# A_D_000000_001.net
KiCad netlist of a schematic drawn in Altium Designer
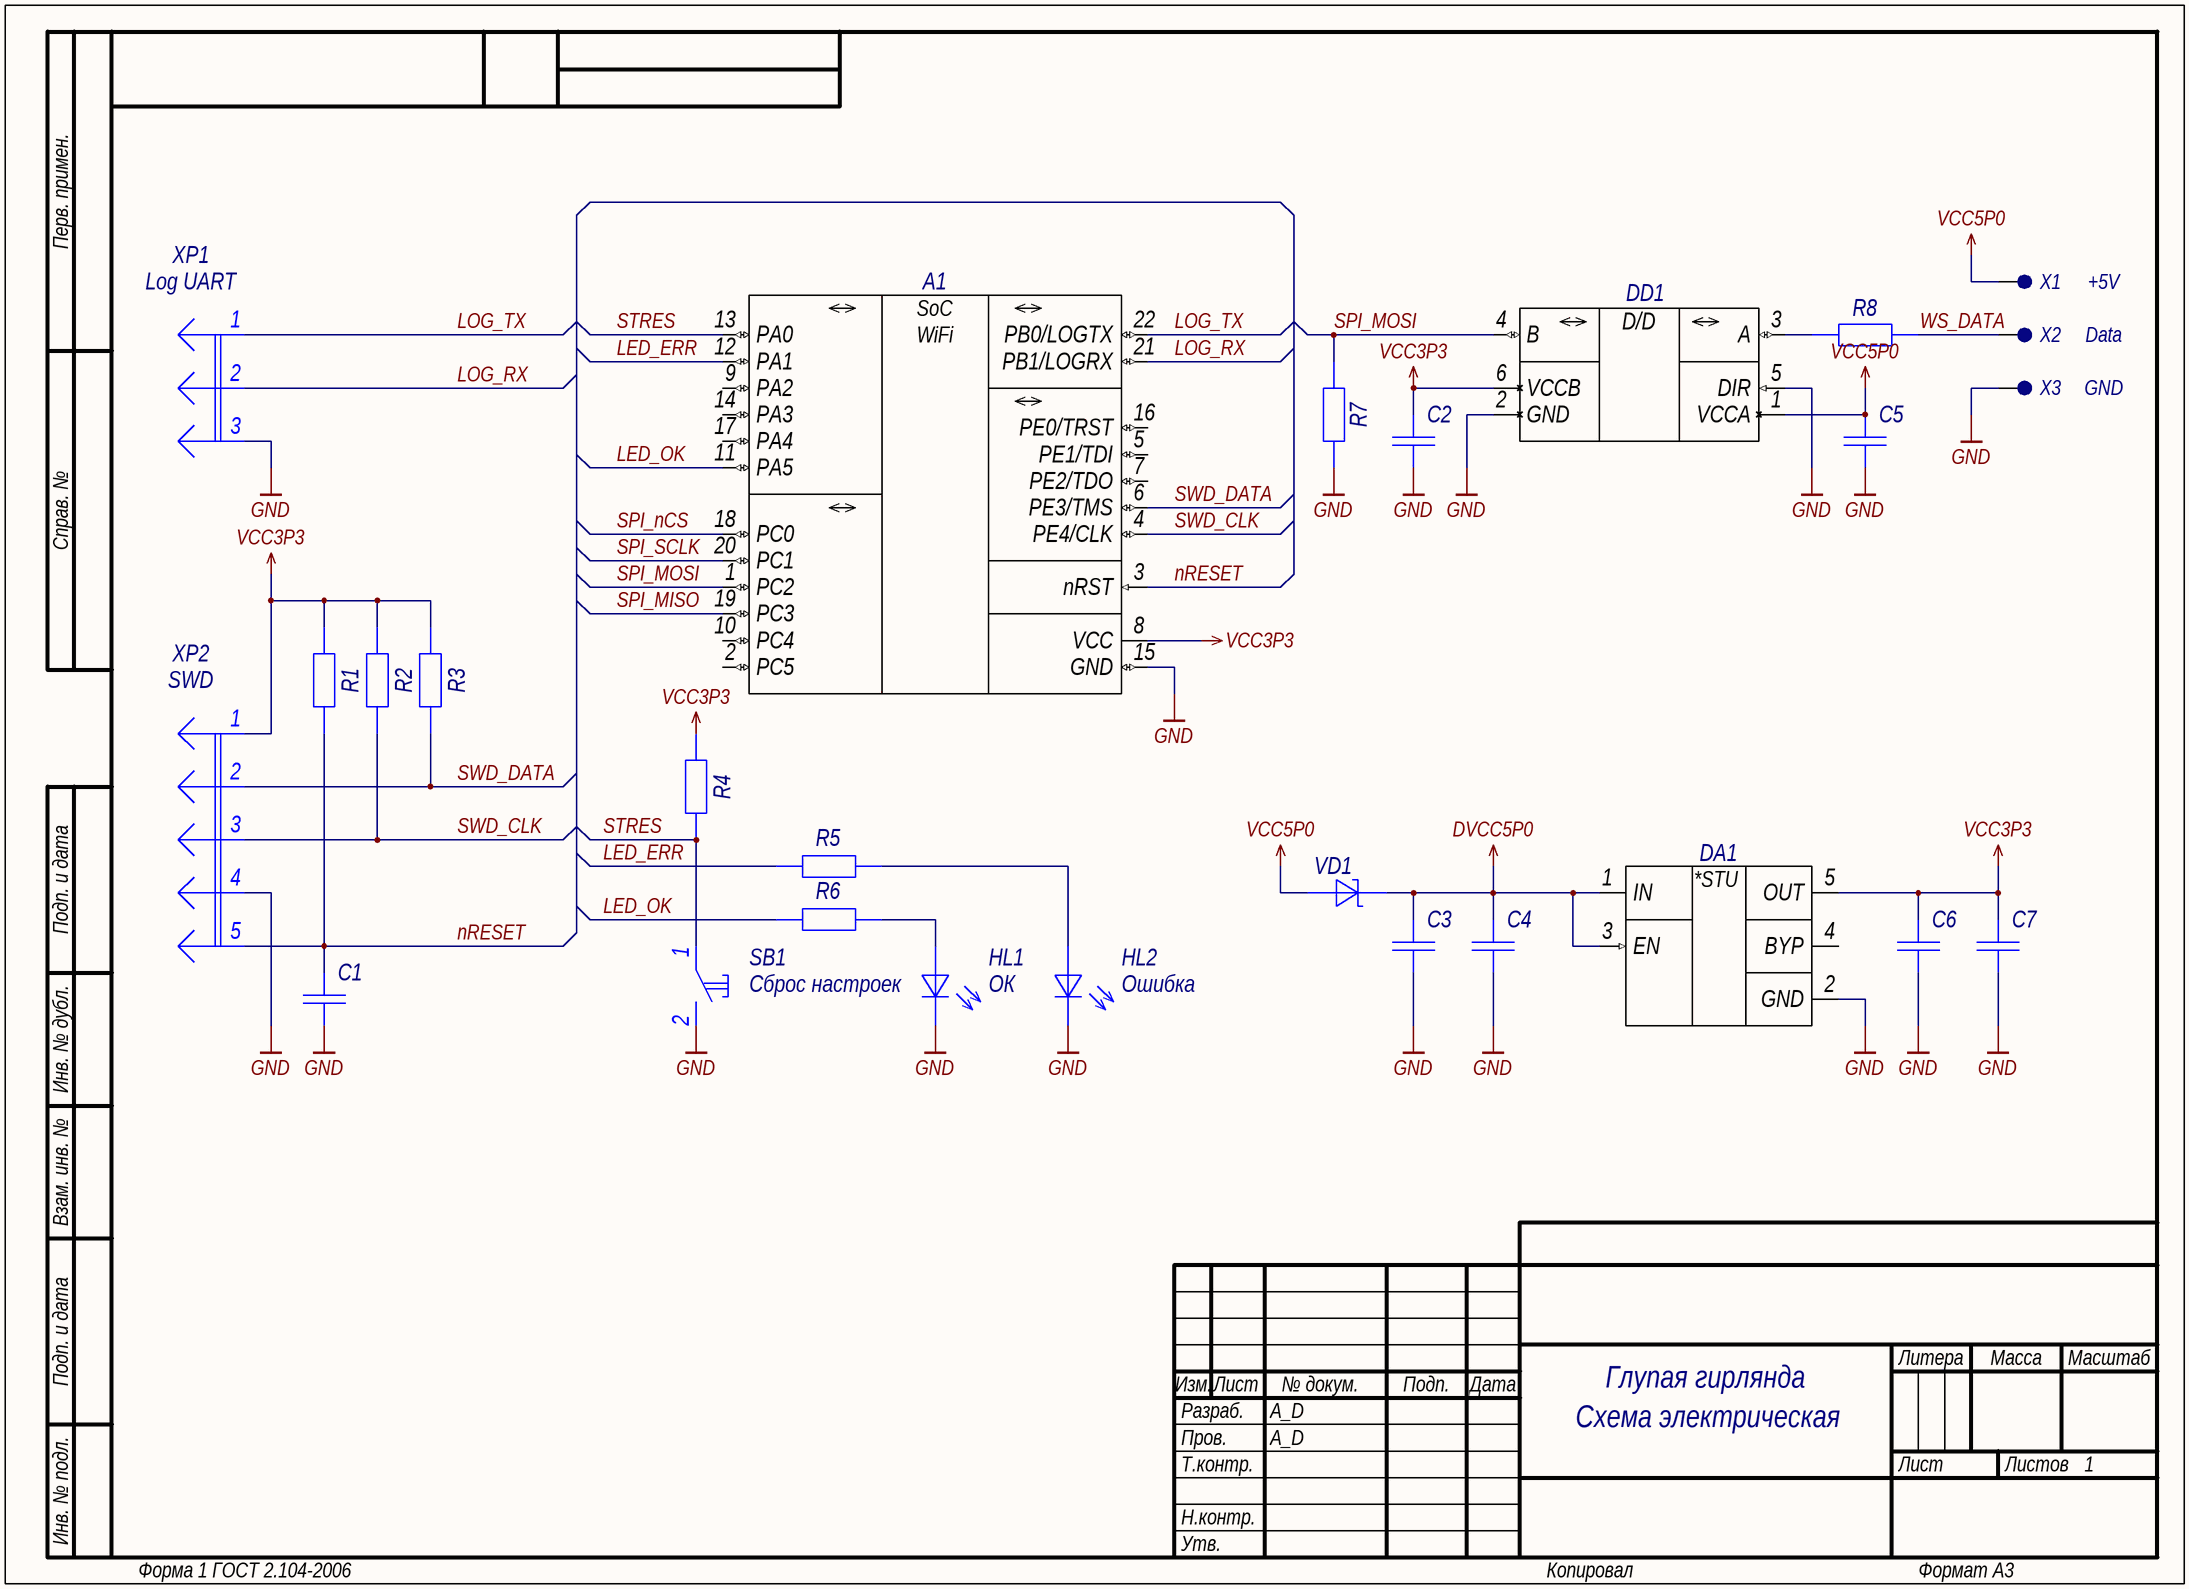
[diagram p0: A_D.000000.001.SchDoc]

(export (version "E")
  (design (tool "Eeschema 10.0.6"))
  (components
    (comp (ref "A1")
      (value "RTL-00_01")
      (footprint "RTL-00")
      (fields
        (field (name "PART NUMBER") "RTL-00")
        (field (name "MANUFACTURER") "B&T")
        (field (name "PUBLISHER") "Andrew Danich")
      )
      (libsource (lib "Lib_IMP_GOST") (part "RTL-00_01"))
    )
    (comp (ref "C1")
      (value "Capacitor")
      (footprint "C0603")
      (fields
        (field (name "PART NUMBER") "GRM188R71C104KA01D")
        (field (name "VOLTAGE") "16V")
        (field (name "TOLERANCE") "±10%")
        (field (name "PUBLISHER") "Andrew Danich")
      )
      (libsource (lib "Lib_IMP_GOST") (part "Capacitor"))
    )
    (comp (ref "C2")
      (value "Capacitor")
      (footprint "C0603")
      (fields
        (field (name "PART NUMBER") "GRM188R71C104KA01D")
        (field (name "VOLTAGE") "16V")
        (field (name "TOLERANCE") "±10%")
        (field (name "PUBLISHER") "Andrew Danich")
      )
      (libsource (lib "Lib_IMP_GOST") (part "Capacitor"))
    )
    (comp (ref "C3")
      (value "Capacitor")
      (footprint "C0805")
      (fields
        (field (name "PART NUMBER") "GRM21BR60J226ME39L")
        (field (name "VOLTAGE") "6.3V")
        (field (name "TOLERANCE") "±20%")
        (field (name "PUBLISHER") "Andrew Danich")
      )
      (libsource (lib "Lib_IMP_GOST") (part "Capacitor"))
    )
    (comp (ref "C4")
      (value "Capacitor")
      (footprint "C0603")
      (fields
        (field (name "PART NUMBER") "GRM188R71C104KA01D")
        (field (name "VOLTAGE") "16V")
        (field (name "TOLERANCE") "±10%")
        (field (name "PUBLISHER") "Andrew Danich")
      )
      (libsource (lib "Lib_IMP_GOST") (part "Capacitor"))
    )
    (comp (ref "C5")
      (value "Capacitor")
      (footprint "C0603")
      (fields
        (field (name "PART NUMBER") "GRM188R71C104KA01D")
        (field (name "VOLTAGE") "16V")
        (field (name "TOLERANCE") "±10%")
        (field (name "PUBLISHER") "Andrew Danich")
      )
      (libsource (lib "Lib_IMP_GOST") (part "Capacitor"))
    )
    (comp (ref "C6")
      (value "Capacitor")
      (footprint "C0603")
      (fields
        (field (name "PART NUMBER") "GRM188R71C104KA01D")
        (field (name "VOLTAGE") "16V")
        (field (name "TOLERANCE") "±10%")
        (field (name "PUBLISHER") "Andrew Danich")
      )
      (libsource (lib "Lib_IMP_GOST") (part "Capacitor"))
    )
    (comp (ref "C7")
      (value "Capacitor")
      (footprint "C0805")
      (fields
        (field (name "PART NUMBER") "GRM21BR60J226ME39L")
        (field (name "VOLTAGE") "6.3V")
        (field (name "TOLERANCE") "±20%")
        (field (name "PUBLISHER") "Andrew Danich")
      )
      (libsource (lib "Lib_IMP_GOST") (part "Capacitor"))
    )
    (comp (ref "DA1")
      (value "MIC5205-Series")
      (footprint "SOT-23-5")
      (fields
        (field (name "PART NUMBER") "MIC5205-3.3YM5")
        (field (name "MANUFACTURER") "Micrel")
        (field (name "PUBLISHER") "Andrew Danich")
      )
      (libsource (lib "Lib_IMP_GOST") (part "MIC5205-Series"))
    )
    (comp (ref "DD1")
      (value "SN74AVC1T45D")
      (footprint "SOT-23-6")
      (fields
        (field (name "PART NUMBER") "SN74AVC1T45DBVR")
        (field (name "MANUFACTURER") "Texas Instruments")
        (field (name "PUBLISHER") "Andrew Danich")
      )
      (libsource (lib "Lib_IMP_GOST") (part "SN74AVC1T45D"))
    )
    (comp (ref "HL1")
      (value "ОК")
      (footprint "LD0603_L")
      (fields (field (name "PART NUMBER") "BL-LS0603GC") (field (name "PUBLISHER") "Andrew Danich"))
      (libsource (lib "Lib_IMP_GOST") (part "Led-1"))
    )
    (comp (ref "HL2")
      (value "Ошибка")
      (footprint "LD0603_L")
      (fields (field (name "PART NUMBER") "BL-LS0603HC") (field (name "PUBLISHER") "Andrew Danich"))
      (libsource (lib "Lib_IMP_GOST") (part "Led-1"))
    )
    (comp (ref "R1")
      (value "Resistor")
      (footprint "R0603")
      (fields
        (field (name "PART NUMBER") "RC0603JR-0710KL")
        (field (name "TOLERANCE") "±5%")
        (field (name "MANUFACTURER") "Yageo")
        (field (name "PUBLISHER") "Andrew Danich")
      )
      (libsource (lib "Lib_IMP_GOST") (part "Resistor"))
    )
    (comp (ref "R2")
      (value "Resistor")
      (footprint "R0603")
      (fields
        (field (name "PART NUMBER") "RC0603JR-0710KL")
        (field (name "TOLERANCE") "±5%")
        (field (name "MANUFACTURER") "Yageo")
        (field (name "PUBLISHER") "Andrew Danich")
      )
      (libsource (lib "Lib_IMP_GOST") (part "Resistor"))
    )
    (comp (ref "R3")
      (value "Resistor")
      (footprint "R0603")
      (fields
        (field (name "PART NUMBER") "RC0603JR-0710KL")
        (field (name "TOLERANCE") "±5%")
        (field (name "MANUFACTURER") "Yageo")
        (field (name "PUBLISHER") "Andrew Danich")
      )
      (libsource (lib "Lib_IMP_GOST") (part "Resistor"))
    )
    (comp (ref "R4")
      (value "Resistor")
      (footprint "R0603_L")
      (fields
        (field (name "PART NUMBER") "RC0603JR-0710KL")
        (field (name "TOLERANCE") "±5%")
        (field (name "MANUFACTURER") "Yageo")
        (field (name "PUBLISHER") "Andrew Danich")
      )
      (libsource (lib "Lib_IMP_GOST") (part "Resistor"))
    )
    (comp (ref "R5")
      (value "Resistor")
      (footprint "R0603_L")
      (fields
        (field (name "PART NUMBER") "RC0603JR-07330RL")
        (field (name "TOLERANCE") "±5%")
        (field (name "MANUFACTURER") "Yageo")
        (field (name "PUBLISHER") "Andrew Danich")
      )
      (libsource (lib "Lib_IMP_GOST") (part "Resistor"))
    )
    (comp (ref "R6")
      (value "Resistor")
      (footprint "R0603_L")
      (fields
        (field (name "PART NUMBER") "RC0603JR-07330RL")
        (field (name "TOLERANCE") "±5%")
        (field (name "MANUFACTURER") "Yageo")
        (field (name "PUBLISHER") "Andrew Danich")
      )
      (libsource (lib "Lib_IMP_GOST") (part "Resistor"))
    )
    (comp (ref "R7")
      (value "Resistor")
      (footprint "R0603_L")
      (fields
        (field (name "PART NUMBER") "RC0603JR-074K7L")
        (field (name "TOLERANCE") "±5%")
        (field (name "MANUFACTURER") "Yageo")
        (field (name "PUBLISHER") "Andrew Danich")
      )
      (libsource (lib "Lib_IMP_GOST") (part "Resistor"))
    )
    (comp (ref "R8")
      (value "Resistor")
      (footprint "R0603")
      (fields
        (field (name "PART NUMBER") "RC0603JR-07100R")
        (field (name "TOLERANCE") "±5%")
        (field (name "MANUFACTURER") "Yageo")
        (field (name "PUBLISHER") "Andrew Danich")
      )
      (libsource (lib "Lib_IMP_GOST") (part "Resistor"))
    )
    (comp (ref "SB1")
      (value "Сброс настроек")
      (footprint "SKQGABE010")
      (fields
        (field (name "PART NUMBER") "SKQGABE010")
        (field (name "MANUFACTURER") "ALPS")
        (field (name "PUBLISHER") "Andrew Danich")
      )
      (libsource (lib "Lib_IMP_GOST") (part "BT-01x-01p"))
    )
    (comp (ref "VD1")
      (value "Schottky")
      (footprint "SOD-123")
      (fields (field (name "PART NUMBER") "SD103CW") (field (name "PUBLISHER") "Andrew Danich"))
      (libsource (lib "Lib_IMP_GOST") (part "Schottky"))
    )
    (comp (ref "X1") (value "+5V") (footprint "SMDPad_4.0") (libsource (lib "Sch") (part "SMDPad")))
    (comp (ref "X2") (value "Data") (footprint "SMDPad_4.0") (libsource (lib "Sch") (part "SMDPad")))
    (comp (ref "X3") (value "GND") (footprint "SMDPad_4.0") (libsource (lib "Sch") (part "SMDPad")))
    (comp (ref "XP1")
      (value "Log UART")
      (footprint "PLS-3")
      (fields (field (name "PART NUMBER") "PLS-3") (field (name "PUBLISHER") "Andrew Danich"))
      (libsource (lib "Lib_IMP_GOST") (part "Con-3-M"))
    )
    (comp (ref "XP2")
      (value "SWD")
      (footprint "PLS-5")
      (fields (field (name "PART NUMBER") "PLS-5") (field (name "PUBLISHER") "Andrew Danich"))
      (libsource (lib "Lib_IMP_GOST") (part "Con-5-M"))
    )
  )
  (nets
    (net (code "1") (name "/LED_ERR") (class "Default")
      (node (ref "A1") (pin "12") (pinfunction "PA1_12") (pintype "bidirectional"))
      (node (ref "R5") (pin "1") (pinfunction "1_1") (pintype "passive"))
    )
    (net (code "2") (name "/LED_OK") (class "Default")
      (node (ref "A1") (pin "11") (pinfunction "PA5_11") (pintype "bidirectional"))
      (node (ref "R6") (pin "1") (pinfunction "1_1") (pintype "passive"))
    )
    (net (code "3") (name "/LOG_RX") (class "Default")
      (node (ref "A1") (pin "21") (pinfunction "PB1/LOGRX_21") (pintype "bidirectional"))
      (node (ref "XP1") (pin "2") (pintype "passive"))
    )
    (net (code "4") (name "/LOG_TX") (class "Default")
      (node (ref "A1") (pin "22") (pinfunction "PB0/LOGTX_22") (pintype "bidirectional"))
      (node (ref "XP1") (pin "1") (pintype "passive"))
    )
    (net (code "5") (name "/SPI_MISO") (class "Default")
      (node (ref "A1") (pin "19") (pinfunction "PC3_19") (pintype "bidirectional"))
    )
    (net (code "6") (name "/SPI_MOSI") (class "Default")
      (node (ref "A1") (pin "1") (pinfunction "PC2_1") (pintype "bidirectional"))
      (node (ref "DD1") (pin "4") (pinfunction "B_4") (pintype "bidirectional"))
      (node (ref "R7") (pin "2") (pinfunction "2_2") (pintype "passive"))
    )
    (net (code "7") (name "/SPI_SCLK") (class "Default")
      (node (ref "A1") (pin "20") (pinfunction "PC1_20") (pintype "bidirectional"))
    )
    (net (code "8") (name "/SPI_nCS") (class "Default")
      (node (ref "A1") (pin "18") (pinfunction "PC0_18") (pintype "bidirectional"))
    )
    (net (code "9") (name "/STRES") (class "Default")
      (node (ref "A1") (pin "13") (pinfunction "PA0_13") (pintype "bidirectional"))
      (node (ref "R4") (pin "1") (pinfunction "1_1") (pintype "passive"))
      (node (ref "SB1") (pin "1") (pintype "passive"))
    )
    (net (code "10") (name "/SWD_CLK") (class "Default")
      (node (ref "A1") (pin "4") (pinfunction "PE4/CLK_4") (pintype "bidirectional"))
      (node (ref "R2") (pin "1") (pinfunction "1_1") (pintype "passive"))
      (node (ref "XP2") (pin "3") (pintype "passive"))
    )
    (net (code "11") (name "/SWD_DATA") (class "Default")
      (node (ref "A1") (pin "6") (pinfunction "PE3/TMS_6") (pintype "bidirectional"))
      (node (ref "R3") (pin "1") (pinfunction "1_1") (pintype "passive"))
      (node (ref "XP2") (pin "2") (pintype "passive"))
    )
    (net (code "12") (name "/WS_DATA") (class "Default")
      (node (ref "R8") (pin "2") (pinfunction "2_2") (pintype "passive"))
      (node (ref "X2") (pin "1") (pinfunction "1_1") (pintype "passive"))
    )
    (net (code "13") (name "/nRESET") (class "Default")
      (node (ref "A1") (pin "3") (pinfunction "nRST_3") (pintype "input"))
      (node (ref "C1") (pin "2") (pinfunction "2_2") (pintype "passive"))
      (node (ref "R1") (pin "1") (pinfunction "1_1") (pintype "passive"))
      (node (ref "XP2") (pin "5") (pintype "passive"))
    )
    (net (code "14") (name "DVCC5P0") (class "Default")
      (node (ref "C3") (pin "2") (pinfunction "2_2") (pintype "passive"))
      (node (ref "C4") (pin "2") (pinfunction "2_2") (pintype "passive"))
      (node (ref "DA1") (pin "1") (pinfunction "IN_1") (pintype "power_in"))
      (node (ref "DA1") (pin "3") (pinfunction "EN_3") (pintype "input"))
      (node (ref "VD1") (pin "2") (pinfunction "К_2") (pintype "passive"))
    )
    (net (code "15") (name "GND") (class "Default")
      (node (ref "A1") (pin "15") (pinfunction "GND_15") (pintype "bidirectional"))
      (node (ref "C1") (pin "1") (pinfunction "1_1") (pintype "passive"))
      (node (ref "C2") (pin "1") (pinfunction "1_1") (pintype "passive"))
      (node (ref "C3") (pin "1") (pinfunction "1_1") (pintype "passive"))
      (node (ref "C4") (pin "1") (pinfunction "1_1") (pintype "passive"))
      (node (ref "C5") (pin "1") (pinfunction "1_1") (pintype "passive"))
      (node (ref "C6") (pin "1") (pinfunction "1_1") (pintype "passive"))
      (node (ref "C7") (pin "1") (pinfunction "1_1") (pintype "passive"))
      (node (ref "DA1") (pin "2") (pinfunction "GND_2") (pintype "power_in"))
      (node (ref "DD1") (pin "2") (pinfunction "GND_2") (pintype "power_in"))
      (node (ref "DD1") (pin "5") (pinfunction "DIR_5") (pintype "input"))
      (node (ref "HL1") (pin "2") (pinfunction "К_2") (pintype "passive"))
      (node (ref "HL2") (pin "2") (pinfunction "К_2") (pintype "passive"))
      (node (ref "R7") (pin "1") (pinfunction "1_1") (pintype "passive"))
      (node (ref "SB1") (pin "2") (pintype "passive"))
      (node (ref "X3") (pin "1") (pinfunction "1_1") (pintype "passive"))
      (node (ref "XP1") (pin "3") (pintype "passive"))
      (node (ref "XP2") (pin "4") (pintype "passive"))
    )
    (net (code "16") (name "Net-(DD1-A)") (class "Default")
      (node (ref "DD1") (pin "3") (pinfunction "A_3") (pintype "bidirectional"))
      (node (ref "R8") (pin "1") (pinfunction "1_1") (pintype "passive"))
    )
    (net (code "17") (name "Net-(HL1-А)") (class "Default")
      (node (ref "HL1") (pin "1") (pinfunction "А_1") (pintype "passive"))
      (node (ref "R6") (pin "2") (pinfunction "2_2") (pintype "passive"))
    )
    (net (code "18") (name "Net-(HL2-А)") (class "Default")
      (node (ref "HL2") (pin "1") (pinfunction "А_1") (pintype "passive"))
      (node (ref "R5") (pin "2") (pinfunction "2_2") (pintype "passive"))
    )
    (net (code "19") (name "VCC3P3") (class "Default")
      (node (ref "A1") (pin "8") (pinfunction "VCC_8") (pintype "power_in"))
      (node (ref "C2") (pin "2") (pinfunction "2_2") (pintype "passive"))
      (node (ref "C6") (pin "2") (pinfunction "2_2") (pintype "passive"))
      (node (ref "C7") (pin "2") (pinfunction "2_2") (pintype "passive"))
      (node (ref "DA1") (pin "5") (pinfunction "OUT_5") (pintype "power_in"))
      (node (ref "DD1") (pin "6") (pinfunction "VCCB_6") (pintype "power_in"))
      (node (ref "R1") (pin "2") (pinfunction "2_2") (pintype "passive"))
      (node (ref "R2") (pin "2") (pinfunction "2_2") (pintype "passive"))
      (node (ref "R3") (pin "2") (pinfunction "2_2") (pintype "passive"))
      (node (ref "R4") (pin "2") (pinfunction "2_2") (pintype "passive"))
      (node (ref "XP2") (pin "1") (pintype "passive"))
    )
    (net (code "20") (name "VCC5P0") (class "Default")
      (node (ref "C5") (pin "2") (pinfunction "2_2") (pintype "passive"))
      (node (ref "DD1") (pin "1") (pinfunction "VCCA_1") (pintype "power_in"))
      (node (ref "VD1") (pin "1") (pinfunction "А_1") (pintype "passive"))
      (node (ref "X1") (pin "1") (pinfunction "1_1") (pintype "passive"))
    )
    (net (code "21") (name "unconnected-(A1-PA2-Pad9)") (class "Default")
      (node (ref "A1") (pin "9") (pinfunction "PA2_9") (pintype "bidirectional"))
    )
    (net (code "22") (name "unconnected-(A1-PA3-Pad14)") (class "Default")
      (node (ref "A1") (pin "14") (pinfunction "PA3_14") (pintype "bidirectional"))
    )
    (net (code "23") (name "unconnected-(A1-PA4-Pad17)") (class "Default")
      (node (ref "A1") (pin "17") (pinfunction "PA4_17") (pintype "bidirectional"))
    )
    (net (code "24") (name "unconnected-(A1-PC4-Pad10)") (class "Default")
      (node (ref "A1") (pin "10") (pinfunction "PC4_10") (pintype "bidirectional"))
    )
    (net (code "25") (name "unconnected-(A1-PC5-Pad2)") (class "Default")
      (node (ref "A1") (pin "2") (pinfunction "PC5_2") (pintype "bidirectional"))
    )
    (net (code "26") (name "unconnected-(A1-PE0{slash}TRST-Pad16)") (class "Default")
      (node (ref "A1") (pin "16") (pinfunction "PE0/TRST_16") (pintype "bidirectional"))
    )
    (net (code "27") (name "unconnected-(A1-PE1{slash}TDI-Pad5)") (class "Default")
      (node (ref "A1") (pin "5") (pinfunction "PE1/TDI_5") (pintype "bidirectional"))
    )
    (net (code "28") (name "unconnected-(A1-PE2{slash}TDO-Pad7)") (class "Default")
      (node (ref "A1") (pin "7") (pinfunction "PE2/TDO_7") (pintype "bidirectional"))
    )
    (net (code "29") (name "unconnected-(DA1-BYP-Pad4)") (class "Default")
      (node (ref "DA1") (pin "4") (pinfunction "BYP_4") (pintype "passive"))
    )
  )
)
